# sensor-board_v1_23.net
KiCad netlist of a schematic drawn in EAGLE
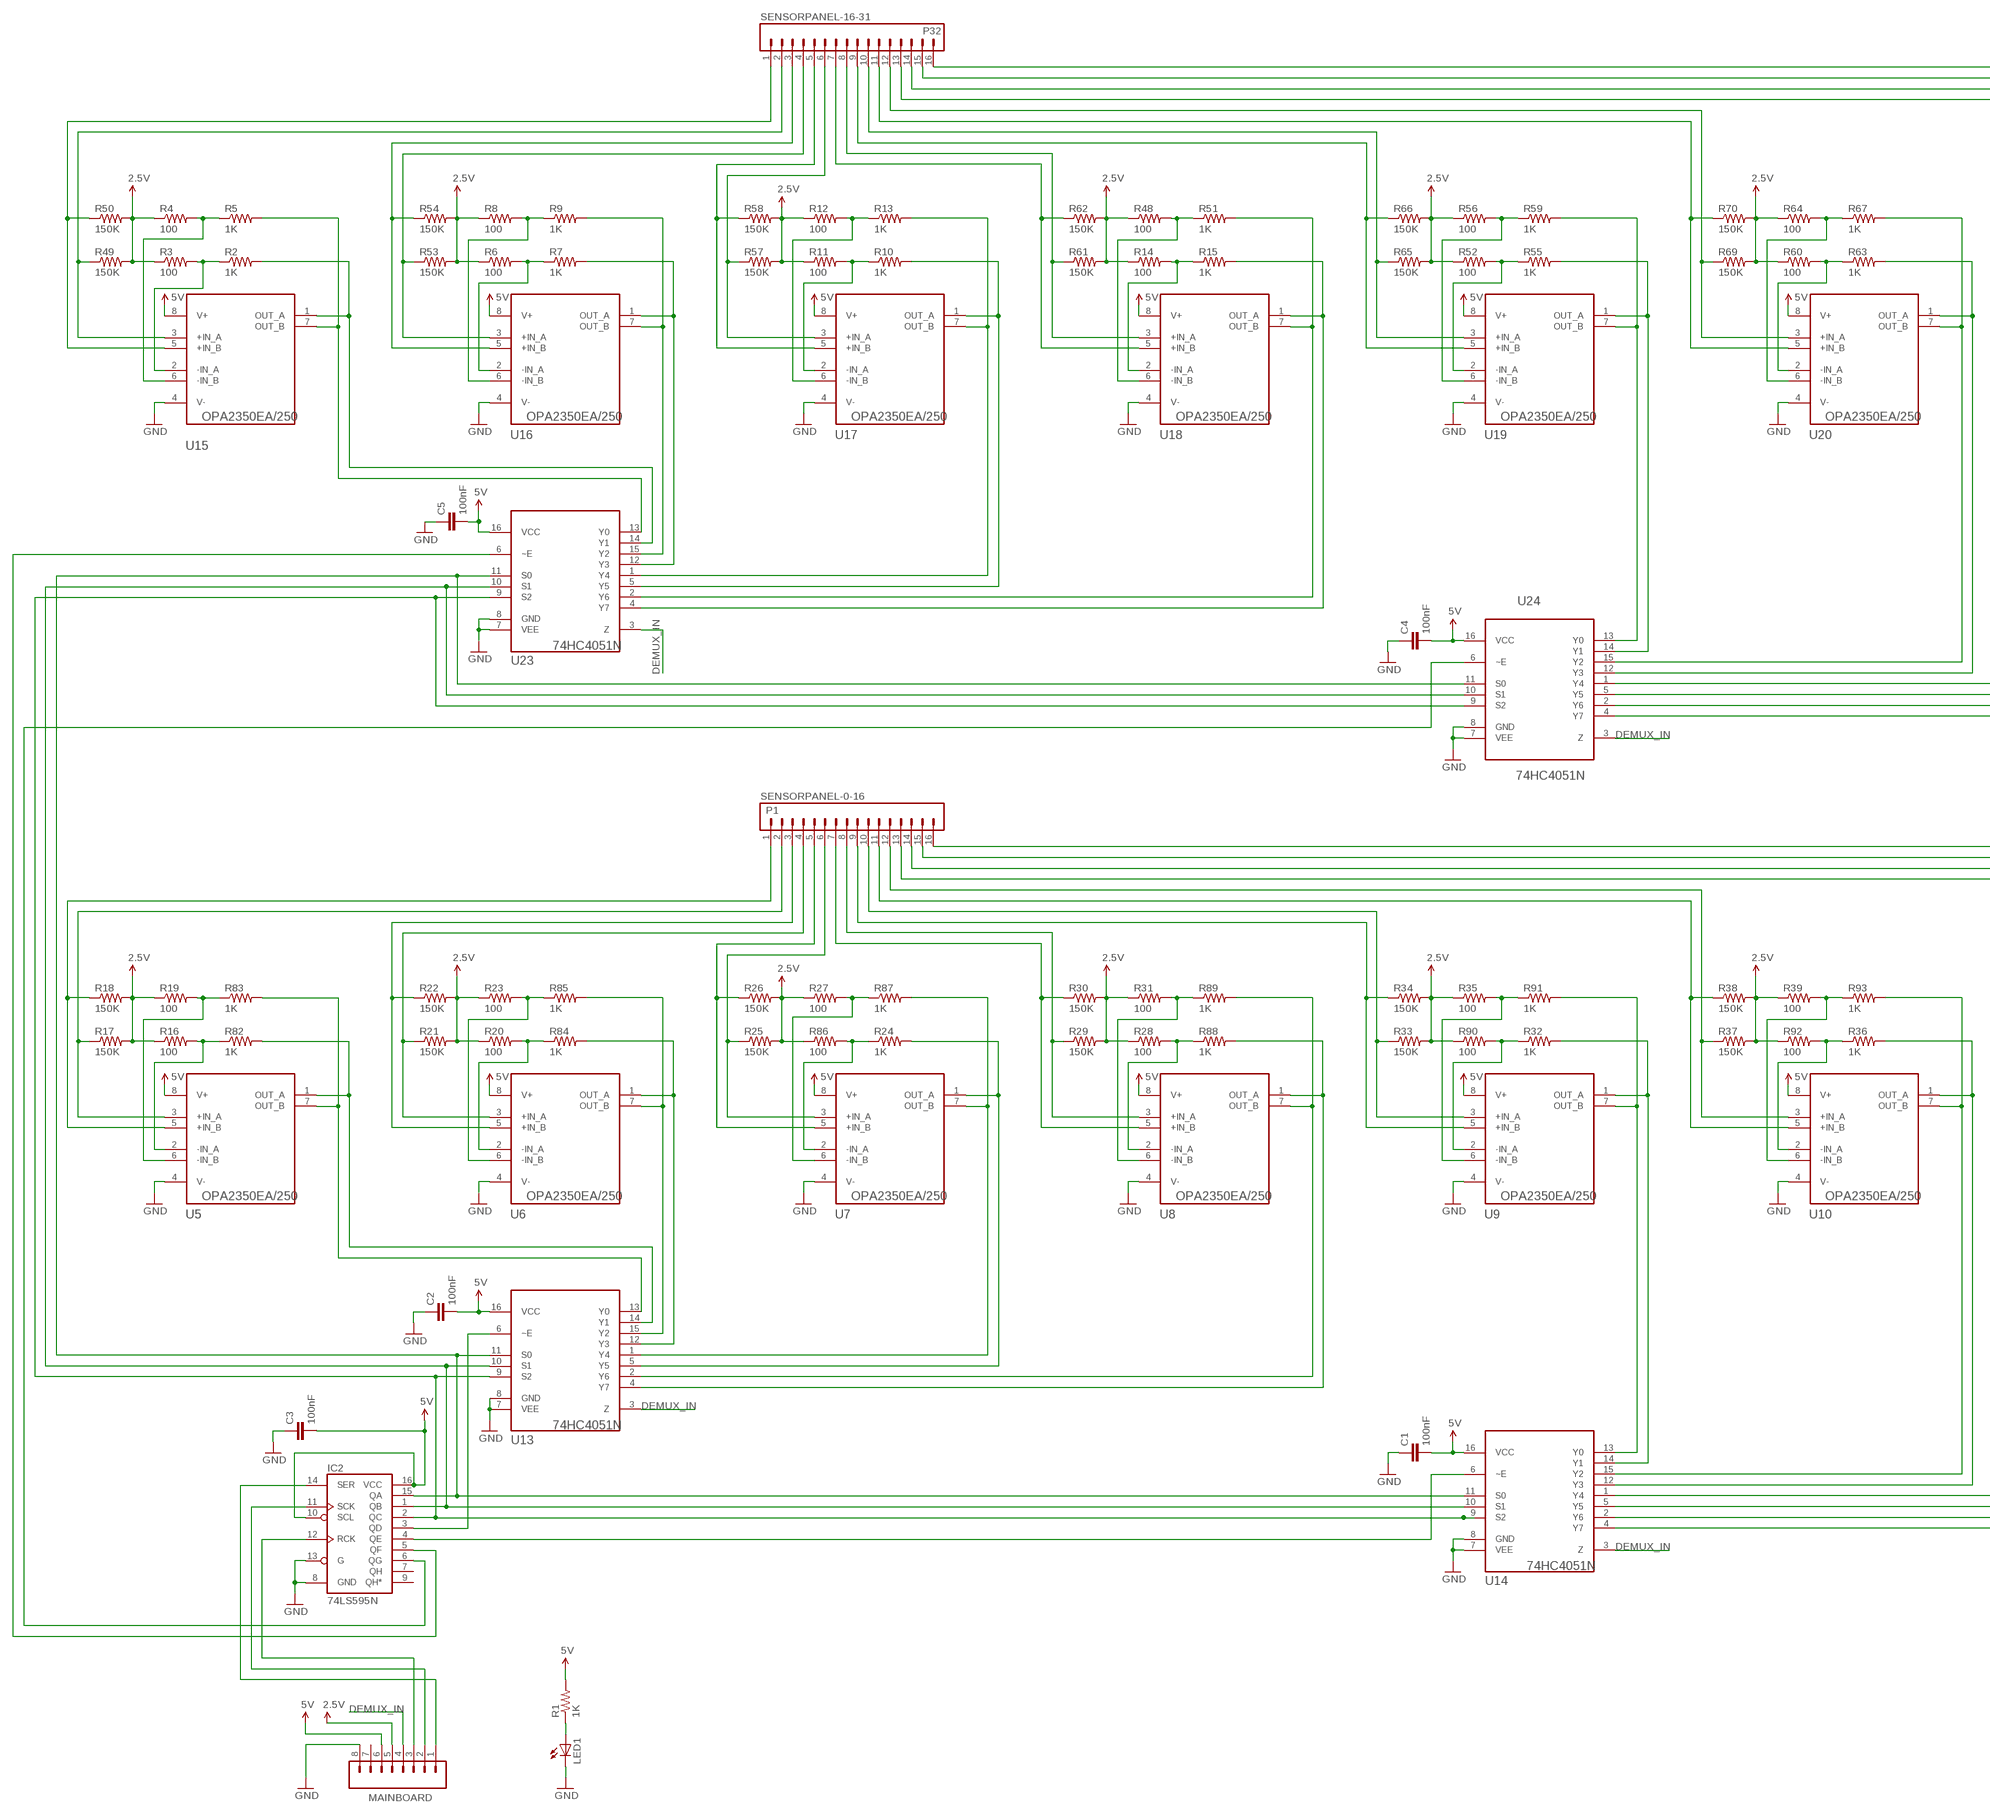
[diagram p0: schematic, sheet 1, part 1 of 2]
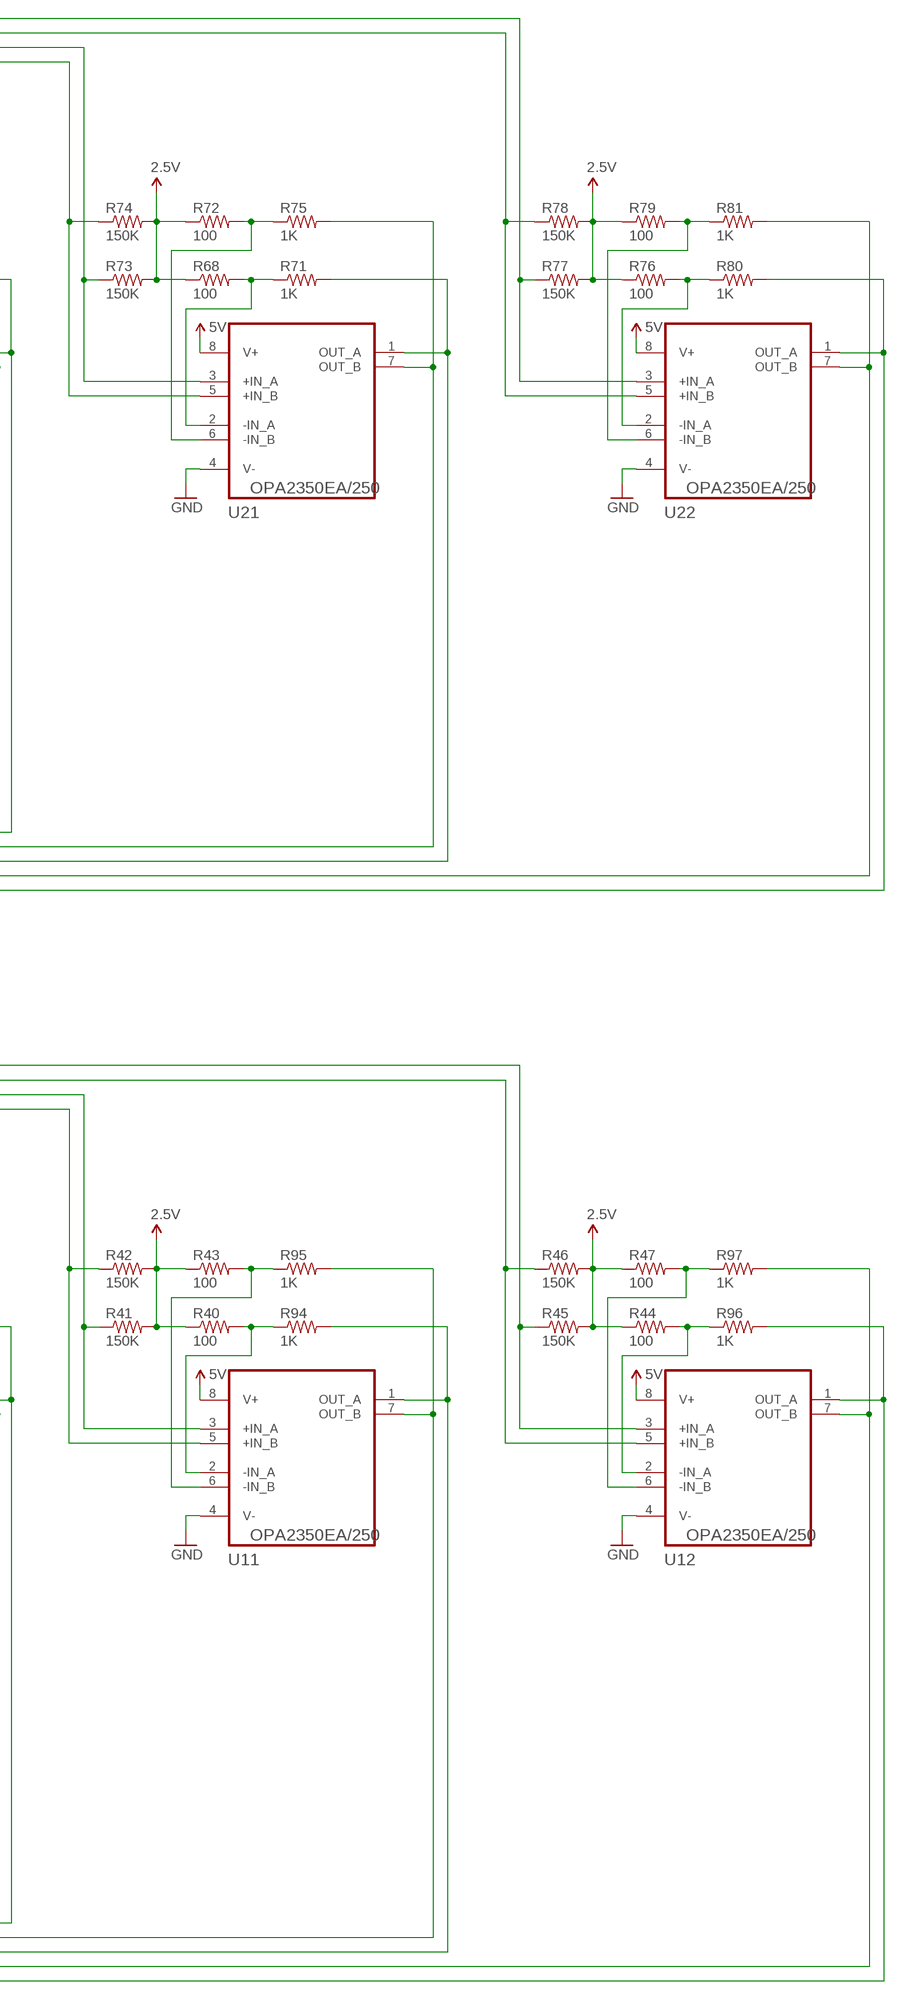
[diagram p1: schematic, sheet 1, part 2 of 2]

(export (version "E")
  (design (tool "Eeschema 10.0.6"))
  (components
    (comp (ref "C1")
      (value "100nF")
      (footprint "eagle-import:CAP-PTH-SMALL")
      (libsource (lib "eagle-import") (part "CAPPTH"))
    )
    (comp (ref "C2")
      (value "100nF")
      (footprint "eagle-import:CAP-PTH-SMALL")
      (libsource (lib "eagle-import") (part "CAPPTH"))
    )
    (comp (ref "C3")
      (value "100nF")
      (footprint "eagle-import:CAP-PTH-SMALL")
      (libsource (lib "eagle-import") (part "CAPPTH"))
    )
    (comp (ref "C4")
      (value "100nF")
      (footprint "eagle-import:CAP-PTH-SMALL")
      (libsource (lib "eagle-import") (part "CAPPTH"))
    )
    (comp (ref "C5")
      (value "100nF")
      (footprint "eagle-import:CAP-PTH-SMALL")
      (libsource (lib "eagle-import") (part "CAPPTH"))
    )
    (comp (ref "IC2")
      (value "74LS595N")
      (footprint "eagle-import:DIL16")
      (libsource (lib "eagle-import") (part "74595NLS"))
    )
    (comp (ref "LED1")
      (value "LED0603")
      (footprint "eagle-import:LED-0603")
      (libsource (lib "eagle-import") (part "LED0603"))
    )
    (comp (ref "MAINBOARD")
      (value "M08LONGPADS")
      (footprint "eagle-import:1X08_LONGPADS")
      (libsource (lib "eagle-import") (part "M08LONGPADS"))
    )
    (comp (ref "R1")
      (value "1K")
      (footprint "eagle-import:0805")
      (libsource (lib "eagle-import") (part "RESISTOR0805-RES"))
    )
    (comp (ref "R2")
      (value "1K")
      (footprint "eagle-import:0805")
      (libsource (lib "eagle-import") (part "RESISTOR0805-RES"))
    )
    (comp (ref "R3")
      (value "100")
      (footprint "eagle-import:0805")
      (libsource (lib "eagle-import") (part "RESISTOR0805-RES"))
    )
    (comp (ref "R4")
      (value "100")
      (footprint "eagle-import:0805")
      (libsource (lib "eagle-import") (part "RESISTOR0805-RES"))
    )
    (comp (ref "R5")
      (value "1K")
      (footprint "eagle-import:0805")
      (libsource (lib "eagle-import") (part "RESISTOR0805-RES"))
    )
    (comp (ref "R6")
      (value "100")
      (footprint "eagle-import:0805")
      (libsource (lib "eagle-import") (part "RESISTOR0805-RES"))
    )
    (comp (ref "R7")
      (value "1K")
      (footprint "eagle-import:0805")
      (libsource (lib "eagle-import") (part "RESISTOR0805-RES"))
    )
    (comp (ref "R8")
      (value "100")
      (footprint "eagle-import:0805")
      (libsource (lib "eagle-import") (part "RESISTOR0805-RES"))
    )
    (comp (ref "R9")
      (value "1K")
      (footprint "eagle-import:0805")
      (libsource (lib "eagle-import") (part "RESISTOR0805-RES"))
    )
    (comp (ref "R10")
      (value "1K")
      (footprint "eagle-import:0805")
      (libsource (lib "eagle-import") (part "RESISTOR0805-RES"))
    )
    (comp (ref "R11")
      (value "100")
      (footprint "eagle-import:0805")
      (libsource (lib "eagle-import") (part "RESISTOR0805-RES"))
    )
    (comp (ref "R12")
      (value "100")
      (footprint "eagle-import:0805")
      (libsource (lib "eagle-import") (part "RESISTOR0805-RES"))
    )
    (comp (ref "R13")
      (value "1K")
      (footprint "eagle-import:0805")
      (libsource (lib "eagle-import") (part "RESISTOR0805-RES"))
    )
    (comp (ref "R14")
      (value "100")
      (footprint "eagle-import:0805")
      (libsource (lib "eagle-import") (part "RESISTOR0805-RES"))
    )
    (comp (ref "R15")
      (value "1K")
      (footprint "eagle-import:0805")
      (libsource (lib "eagle-import") (part "RESISTOR0805-RES"))
    )
    (comp (ref "R16")
      (value "100")
      (footprint "eagle-import:0805")
      (libsource (lib "eagle-import") (part "RESISTOR0805-RES"))
    )
    (comp (ref "R17")
      (value "150K")
      (footprint "eagle-import:0805")
      (libsource (lib "eagle-import") (part "RESISTOR0805-RES"))
    )
    (comp (ref "R18")
      (value "150K")
      (footprint "eagle-import:0805")
      (libsource (lib "eagle-import") (part "RESISTOR0805-RES"))
    )
    (comp (ref "R19")
      (value "100")
      (footprint "eagle-import:0805")
      (libsource (lib "eagle-import") (part "RESISTOR0805-RES"))
    )
    (comp (ref "R20")
      (value "100")
      (footprint "eagle-import:0805")
      (libsource (lib "eagle-import") (part "RESISTOR0805-RES"))
    )
    (comp (ref "R21")
      (value "150K")
      (footprint "eagle-import:0805")
      (libsource (lib "eagle-import") (part "RESISTOR0805-RES"))
    )
    (comp (ref "R22")
      (value "150K")
      (footprint "eagle-import:0805")
      (libsource (lib "eagle-import") (part "RESISTOR0805-RES"))
    )
    (comp (ref "R23")
      (value "100")
      (footprint "eagle-import:0805")
      (libsource (lib "eagle-import") (part "RESISTOR0805-RES"))
    )
    (comp (ref "R24")
      (value "1K")
      (footprint "eagle-import:0805")
      (libsource (lib "eagle-import") (part "RESISTOR0805-RES"))
    )
    (comp (ref "R25")
      (value "150K")
      (footprint "eagle-import:0805")
      (libsource (lib "eagle-import") (part "RESISTOR0805-RES"))
    )
    (comp (ref "R26")
      (value "150K")
      (footprint "eagle-import:0805")
      (libsource (lib "eagle-import") (part "RESISTOR0805-RES"))
    )
    (comp (ref "R27")
      (value "100")
      (footprint "eagle-import:0805")
      (libsource (lib "eagle-import") (part "RESISTOR0805-RES"))
    )
    (comp (ref "R28")
      (value "100")
      (footprint "eagle-import:0805")
      (libsource (lib "eagle-import") (part "RESISTOR0805-RES"))
    )
    (comp (ref "R29")
      (value "150K")
      (footprint "eagle-import:0805")
      (libsource (lib "eagle-import") (part "RESISTOR0805-RES"))
    )
    (comp (ref "R30")
      (value "150K")
      (footprint "eagle-import:0805")
      (libsource (lib "eagle-import") (part "RESISTOR0805-RES"))
    )
    (comp (ref "R31")
      (value "100")
      (footprint "eagle-import:0805")
      (libsource (lib "eagle-import") (part "RESISTOR0805-RES"))
    )
    (comp (ref "R32")
      (value "1K")
      (footprint "eagle-import:0805")
      (libsource (lib "eagle-import") (part "RESISTOR0805-RES"))
    )
    (comp (ref "R33")
      (value "150K")
      (footprint "eagle-import:0805")
      (libsource (lib "eagle-import") (part "RESISTOR0805-RES"))
    )
    (comp (ref "R34")
      (value "150K")
      (footprint "eagle-import:0805")
      (libsource (lib "eagle-import") (part "RESISTOR0805-RES"))
    )
    (comp (ref "R35")
      (value "100")
      (footprint "eagle-import:0805")
      (libsource (lib "eagle-import") (part "RESISTOR0805-RES"))
    )
    (comp (ref "R36")
      (value "1K")
      (footprint "eagle-import:0805")
      (libsource (lib "eagle-import") (part "RESISTOR0805-RES"))
    )
    (comp (ref "R37")
      (value "150K")
      (footprint "eagle-import:0805")
      (libsource (lib "eagle-import") (part "RESISTOR0805-RES"))
    )
    (comp (ref "R38")
      (value "150K")
      (footprint "eagle-import:0805")
      (libsource (lib "eagle-import") (part "RESISTOR0805-RES"))
    )
    (comp (ref "R39")
      (value "100")
      (footprint "eagle-import:0805")
      (libsource (lib "eagle-import") (part "RESISTOR0805-RES"))
    )
    (comp (ref "R40")
      (value "100")
      (footprint "eagle-import:0805")
      (libsource (lib "eagle-import") (part "RESISTOR0805-RES"))
    )
    (comp (ref "R41")
      (value "150K")
      (footprint "eagle-import:0805")
      (libsource (lib "eagle-import") (part "RESISTOR0805-RES"))
    )
    (comp (ref "R42")
      (value "150K")
      (footprint "eagle-import:0805")
      (libsource (lib "eagle-import") (part "RESISTOR0805-RES"))
    )
    (comp (ref "R43")
      (value "100")
      (footprint "eagle-import:0805")
      (libsource (lib "eagle-import") (part "RESISTOR0805-RES"))
    )
    (comp (ref "R44")
      (value "100")
      (footprint "eagle-import:0805")
      (libsource (lib "eagle-import") (part "RESISTOR0805-RES"))
    )
    (comp (ref "R45")
      (value "150K")
      (footprint "eagle-import:0805")
      (libsource (lib "eagle-import") (part "RESISTOR0805-RES"))
    )
    (comp (ref "R46")
      (value "150K")
      (footprint "eagle-import:0805")
      (libsource (lib "eagle-import") (part "RESISTOR0805-RES"))
    )
    (comp (ref "R47")
      (value "100")
      (footprint "eagle-import:0805")
      (libsource (lib "eagle-import") (part "RESISTOR0805-RES"))
    )
    (comp (ref "R48")
      (value "100")
      (footprint "eagle-import:0805")
      (libsource (lib "eagle-import") (part "RESISTOR0805-RES"))
    )
    (comp (ref "R49")
      (value "150K")
      (footprint "eagle-import:0805")
      (libsource (lib "eagle-import") (part "RESISTOR0805-RES"))
    )
    (comp (ref "R50")
      (value "150K")
      (footprint "eagle-import:0805")
      (libsource (lib "eagle-import") (part "RESISTOR0805-RES"))
    )
    (comp (ref "R51")
      (value "1K")
      (footprint "eagle-import:0805")
      (libsource (lib "eagle-import") (part "RESISTOR0805-RES"))
    )
    (comp (ref "R52")
      (value "100")
      (footprint "eagle-import:0805")
      (libsource (lib "eagle-import") (part "RESISTOR0805-RES"))
    )
    (comp (ref "R53")
      (value "150K")
      (footprint "eagle-import:0805")
      (libsource (lib "eagle-import") (part "RESISTOR0805-RES"))
    )
    (comp (ref "R54")
      (value "150K")
      (footprint "eagle-import:0805")
      (libsource (lib "eagle-import") (part "RESISTOR0805-RES"))
    )
    (comp (ref "R55")
      (value "1K")
      (footprint "eagle-import:0805")
      (libsource (lib "eagle-import") (part "RESISTOR0805-RES"))
    )
    (comp (ref "R56")
      (value "100")
      (footprint "eagle-import:0805")
      (libsource (lib "eagle-import") (part "RESISTOR0805-RES"))
    )
    (comp (ref "R57")
      (value "150K")
      (footprint "eagle-import:0805")
      (libsource (lib "eagle-import") (part "RESISTOR0805-RES"))
    )
    (comp (ref "R58")
      (value "150K")
      (footprint "eagle-import:0805")
      (libsource (lib "eagle-import") (part "RESISTOR0805-RES"))
    )
    (comp (ref "R59")
      (value "1K")
      (footprint "eagle-import:0805")
      (libsource (lib "eagle-import") (part "RESISTOR0805-RES"))
    )
    (comp (ref "R60")
      (value "100")
      (footprint "eagle-import:0805")
      (libsource (lib "eagle-import") (part "RESISTOR0805-RES"))
    )
    (comp (ref "R61")
      (value "150K")
      (footprint "eagle-import:0805")
      (libsource (lib "eagle-import") (part "RESISTOR0805-RES"))
    )
    (comp (ref "R62")
      (value "150K")
      (footprint "eagle-import:0805")
      (libsource (lib "eagle-import") (part "RESISTOR0805-RES"))
    )
    (comp (ref "R63")
      (value "1K")
      (footprint "eagle-import:0805")
      (libsource (lib "eagle-import") (part "RESISTOR0805-RES"))
    )
    (comp (ref "R64")
      (value "100")
      (footprint "eagle-import:0805")
      (libsource (lib "eagle-import") (part "RESISTOR0805-RES"))
    )
    (comp (ref "R65")
      (value "150K")
      (footprint "eagle-import:0805")
      (libsource (lib "eagle-import") (part "RESISTOR0805-RES"))
    )
    (comp (ref "R66")
      (value "150K")
      (footprint "eagle-import:0805")
      (libsource (lib "eagle-import") (part "RESISTOR0805-RES"))
    )
    (comp (ref "R67")
      (value "1K")
      (footprint "eagle-import:0805")
      (libsource (lib "eagle-import") (part "RESISTOR0805-RES"))
    )
    (comp (ref "R68")
      (value "100")
      (footprint "eagle-import:0805")
      (libsource (lib "eagle-import") (part "RESISTOR0805-RES"))
    )
    (comp (ref "R69")
      (value "150K")
      (footprint "eagle-import:0805")
      (libsource (lib "eagle-import") (part "RESISTOR0805-RES"))
    )
    (comp (ref "R70")
      (value "150K")
      (footprint "eagle-import:0805")
      (libsource (lib "eagle-import") (part "RESISTOR0805-RES"))
    )
    (comp (ref "R71")
      (value "1K")
      (footprint "eagle-import:0805")
      (libsource (lib "eagle-import") (part "RESISTOR0805-RES"))
    )
    (comp (ref "R72")
      (value "100")
      (footprint "eagle-import:0805")
      (libsource (lib "eagle-import") (part "RESISTOR0805-RES"))
    )
    (comp (ref "R73")
      (value "150K")
      (footprint "eagle-import:0805")
      (libsource (lib "eagle-import") (part "RESISTOR0805-RES"))
    )
    (comp (ref "R74")
      (value "150K")
      (footprint "eagle-import:0805")
      (libsource (lib "eagle-import") (part "RESISTOR0805-RES"))
    )
    (comp (ref "R75")
      (value "1K")
      (footprint "eagle-import:0805")
      (libsource (lib "eagle-import") (part "RESISTOR0805-RES"))
    )
    (comp (ref "R76")
      (value "100")
      (footprint "eagle-import:0805")
      (libsource (lib "eagle-import") (part "RESISTOR0805-RES"))
    )
    (comp (ref "R77")
      (value "150K")
      (footprint "eagle-import:0805")
      (libsource (lib "eagle-import") (part "RESISTOR0805-RES"))
    )
    (comp (ref "R78")
      (value "150K")
      (footprint "eagle-import:0805")
      (libsource (lib "eagle-import") (part "RESISTOR0805-RES"))
    )
    (comp (ref "R79")
      (value "100")
      (footprint "eagle-import:0805")
      (libsource (lib "eagle-import") (part "RESISTOR0805-RES"))
    )
    (comp (ref "R80")
      (value "1K")
      (footprint "eagle-import:0805")
      (libsource (lib "eagle-import") (part "RESISTOR0805-RES"))
    )
    (comp (ref "R81")
      (value "1K")
      (footprint "eagle-import:0805")
      (libsource (lib "eagle-import") (part "RESISTOR0805-RES"))
    )
    (comp (ref "R82")
      (value "1K")
      (footprint "eagle-import:0805")
      (libsource (lib "eagle-import") (part "RESISTOR0805-RES"))
    )
    (comp (ref "R83")
      (value "1K")
      (footprint "eagle-import:0805")
      (libsource (lib "eagle-import") (part "RESISTOR0805-RES"))
    )
    (comp (ref "R84")
      (value "1K")
      (footprint "eagle-import:0805")
      (libsource (lib "eagle-import") (part "RESISTOR0805-RES"))
    )
    (comp (ref "R85")
      (value "1K")
      (footprint "eagle-import:0805")
      (libsource (lib "eagle-import") (part "RESISTOR0805-RES"))
    )
    (comp (ref "R86")
      (value "100")
      (footprint "eagle-import:0805")
      (libsource (lib "eagle-import") (part "RESISTOR0805-RES"))
    )
    (comp (ref "R87")
      (value "1K")
      (footprint "eagle-import:0805")
      (libsource (lib "eagle-import") (part "RESISTOR0805-RES"))
    )
    (comp (ref "R88")
      (value "1K")
      (footprint "eagle-import:0805")
      (libsource (lib "eagle-import") (part "RESISTOR0805-RES"))
    )
    (comp (ref "R89")
      (value "1K")
      (footprint "eagle-import:0805")
      (libsource (lib "eagle-import") (part "RESISTOR0805-RES"))
    )
    (comp (ref "R90")
      (value "100")
      (footprint "eagle-import:0805")
      (libsource (lib "eagle-import") (part "RESISTOR0805-RES"))
    )
    (comp (ref "R91")
      (value "1K")
      (footprint "eagle-import:0805")
      (libsource (lib "eagle-import") (part "RESISTOR0805-RES"))
    )
    (comp (ref "R92")
      (value "100")
      (footprint "eagle-import:0805")
      (libsource (lib "eagle-import") (part "RESISTOR0805-RES"))
    )
    (comp (ref "R93")
      (value "1K")
      (footprint "eagle-import:0805")
      (libsource (lib "eagle-import") (part "RESISTOR0805-RES"))
    )
    (comp (ref "R94")
      (value "1K")
      (footprint "eagle-import:0805")
      (libsource (lib "eagle-import") (part "RESISTOR0805-RES"))
    )
    (comp (ref "R95")
      (value "1K")
      (footprint "eagle-import:0805")
      (libsource (lib "eagle-import") (part "RESISTOR0805-RES"))
    )
    (comp (ref "R96")
      (value "1K")
      (footprint "eagle-import:0805")
      (libsource (lib "eagle-import") (part "RESISTOR0805-RES"))
    )
    (comp (ref "R97")
      (value "1K")
      (footprint "eagle-import:0805")
      (libsource (lib "eagle-import") (part "RESISTOR0805-RES"))
    )
    (comp (ref "SENSORPANEL-0-16")
      (value "P1")
      (footprint "eagle-import:1X16_LOCK")
      (libsource (lib "eagle-import") (part "M16LOCK"))
    )
    (comp (ref "SENSORPANEL-16-31")
      (value "P32")
      (footprint "eagle-import:1X16_LOCK")
      (libsource (lib "eagle-import") (part "M16LOCK"))
    )
    (comp (ref "U5")
      (value "OPA2350EA/250")
      (footprint "eagle-import:SOP65P490X110-8N")
      (libsource (lib "eagle-import") (part "OPA2350EA/250"))
    )
    (comp (ref "U6")
      (value "OPA2350EA/250")
      (footprint "eagle-import:SOP65P490X110-8N")
      (libsource (lib "eagle-import") (part "OPA2350EA/250"))
    )
    (comp (ref "U7")
      (value "OPA2350EA/250")
      (footprint "eagle-import:SOP65P490X110-8N")
      (libsource (lib "eagle-import") (part "OPA2350EA/250"))
    )
    (comp (ref "U8")
      (value "OPA2350EA/250")
      (footprint "eagle-import:SOP65P490X110-8N")
      (libsource (lib "eagle-import") (part "OPA2350EA/250"))
    )
    (comp (ref "U9")
      (value "OPA2350EA/250")
      (footprint "eagle-import:SOP65P490X110-8N")
      (libsource (lib "eagle-import") (part "OPA2350EA/250"))
    )
    (comp (ref "U10")
      (value "OPA2350EA/250")
      (footprint "eagle-import:SOP65P490X110-8N")
      (libsource (lib "eagle-import") (part "OPA2350EA/250"))
    )
    (comp (ref "U11")
      (value "OPA2350EA/250")
      (footprint "eagle-import:SOP65P490X110-8N")
      (libsource (lib "eagle-import") (part "OPA2350EA/250"))
    )
    (comp (ref "U12")
      (value "OPA2350EA/250")
      (footprint "eagle-import:SOP65P490X110-8N")
      (libsource (lib "eagle-import") (part "OPA2350EA/250"))
    )
    (comp (ref "U13")
      (value "74HC4051N")
      (footprint "eagle-import:DIP254P762X420-16")
      (libsource (lib "eagle-import") (part "74HC4051N"))
    )
    (comp (ref "U14")
      (value "74HC4051N")
      (footprint "eagle-import:DIP254P762X420-16")
      (libsource (lib "eagle-import") (part "74HC4051N"))
    )
    (comp (ref "U15")
      (value "OPA2350EA/250")
      (footprint "eagle-import:SOP65P490X110-8N")
      (libsource (lib "eagle-import") (part "OPA2350EA/250"))
    )
    (comp (ref "U16")
      (value "OPA2350EA/250")
      (footprint "eagle-import:SOP65P490X110-8N")
      (libsource (lib "eagle-import") (part "OPA2350EA/250"))
    )
    (comp (ref "U17")
      (value "OPA2350EA/250")
      (footprint "eagle-import:SOP65P490X110-8N")
      (libsource (lib "eagle-import") (part "OPA2350EA/250"))
    )
    (comp (ref "U18")
      (value "OPA2350EA/250")
      (footprint "eagle-import:SOP65P490X110-8N")
      (libsource (lib "eagle-import") (part "OPA2350EA/250"))
    )
    (comp (ref "U19")
      (value "OPA2350EA/250")
      (footprint "eagle-import:SOP65P490X110-8N")
      (libsource (lib "eagle-import") (part "OPA2350EA/250"))
    )
    (comp (ref "U20")
      (value "OPA2350EA/250")
      (footprint "eagle-import:SOP65P490X110-8N")
      (libsource (lib "eagle-import") (part "OPA2350EA/250"))
    )
    (comp (ref "U21")
      (value "OPA2350EA/250")
      (footprint "eagle-import:SOP65P490X110-8N")
      (libsource (lib "eagle-import") (part "OPA2350EA/250"))
    )
    (comp (ref "U22")
      (value "OPA2350EA/250")
      (footprint "eagle-import:SOP65P490X110-8N")
      (libsource (lib "eagle-import") (part "OPA2350EA/250"))
    )
    (comp (ref "U23")
      (value "74HC4051N")
      (footprint "eagle-import:DIP254P762X420-16")
      (libsource (lib "eagle-import") (part "74HC4051N"))
    )
    (comp (ref "U24")
      (value "74HC4051N")
      (footprint "eagle-import:DIP254P762X420-16")
      (libsource (lib "eagle-import") (part "74HC4051N"))
    )
  )
  (nets
    (net (code "1") (name "/DEMUX_IN") (class "Default")
      (node (ref "MAINBOARD") (pin "4") (pinfunction "4_4") (pintype "passive"))
      (node (ref "U13") (pin "3") (pinfunction "Z_3") (pintype "bidirectional"))
      (node (ref "U14") (pin "3") (pinfunction "Z_3") (pintype "bidirectional"))
      (node (ref "U23") (pin "3") (pinfunction "Z_3") (pintype "bidirectional"))
      (node (ref "U24") (pin "3") (pinfunction "Z_3") (pintype "bidirectional"))
    )
    (net (code "2") (name "2.5V") (class "Default")
      (node (ref "MAINBOARD") (pin "5") (pinfunction "5_5") (pintype "passive"))
      (node (ref "R11") (pin "1") (pinfunction "1_1") (pintype "passive"))
      (node (ref "R12") (pin "1") (pinfunction "1_1") (pintype "passive"))
      (node (ref "R14") (pin "1") (pinfunction "1_1") (pintype "passive"))
      (node (ref "R16") (pin "1") (pinfunction "1_1") (pintype "passive"))
      (node (ref "R17") (pin "2") (pinfunction "2_2") (pintype "passive"))
      (node (ref "R18") (pin "2") (pinfunction "2_2") (pintype "passive"))
      (node (ref "R19") (pin "1") (pinfunction "1_1") (pintype "passive"))
      (node (ref "R20") (pin "1") (pinfunction "1_1") (pintype "passive"))
      (node (ref "R21") (pin "2") (pinfunction "2_2") (pintype "passive"))
      (node (ref "R22") (pin "2") (pinfunction "2_2") (pintype "passive"))
      (node (ref "R23") (pin "1") (pinfunction "1_1") (pintype "passive"))
      (node (ref "R25") (pin "2") (pinfunction "2_2") (pintype "passive"))
      (node (ref "R26") (pin "2") (pinfunction "2_2") (pintype "passive"))
      (node (ref "R27") (pin "1") (pinfunction "1_1") (pintype "passive"))
      (node (ref "R28") (pin "1") (pinfunction "1_1") (pintype "passive"))
      (node (ref "R29") (pin "2") (pinfunction "2_2") (pintype "passive"))
      (node (ref "R3") (pin "1") (pinfunction "1_1") (pintype "passive"))
      (node (ref "R30") (pin "2") (pinfunction "2_2") (pintype "passive"))
      (node (ref "R31") (pin "1") (pinfunction "1_1") (pintype "passive"))
      (node (ref "R33") (pin "2") (pinfunction "2_2") (pintype "passive"))
      (node (ref "R34") (pin "2") (pinfunction "2_2") (pintype "passive"))
      (node (ref "R35") (pin "1") (pinfunction "1_1") (pintype "passive"))
      (node (ref "R37") (pin "2") (pinfunction "2_2") (pintype "passive"))
      (node (ref "R38") (pin "2") (pinfunction "2_2") (pintype "passive"))
      (node (ref "R39") (pin "1") (pinfunction "1_1") (pintype "passive"))
      (node (ref "R4") (pin "1") (pinfunction "1_1") (pintype "passive"))
      (node (ref "R40") (pin "1") (pinfunction "1_1") (pintype "passive"))
      (node (ref "R41") (pin "2") (pinfunction "2_2") (pintype "passive"))
      (node (ref "R42") (pin "2") (pinfunction "2_2") (pintype "passive"))
      (node (ref "R43") (pin "1") (pinfunction "1_1") (pintype "passive"))
      (node (ref "R44") (pin "1") (pinfunction "1_1") (pintype "passive"))
      (node (ref "R45") (pin "2") (pinfunction "2_2") (pintype "passive"))
      (node (ref "R46") (pin "2") (pinfunction "2_2") (pintype "passive"))
      (node (ref "R47") (pin "1") (pinfunction "1_1") (pintype "passive"))
      (node (ref "R48") (pin "1") (pinfunction "1_1") (pintype "passive"))
      (node (ref "R49") (pin "2") (pinfunction "2_2") (pintype "passive"))
      (node (ref "R50") (pin "2") (pinfunction "2_2") (pintype "passive"))
      (node (ref "R52") (pin "1") (pinfunction "1_1") (pintype "passive"))
      (node (ref "R53") (pin "2") (pinfunction "2_2") (pintype "passive"))
      (node (ref "R54") (pin "2") (pinfunction "2_2") (pintype "passive"))
      (node (ref "R56") (pin "1") (pinfunction "1_1") (pintype "passive"))
      (node (ref "R57") (pin "2") (pinfunction "2_2") (pintype "passive"))
      (node (ref "R58") (pin "2") (pinfunction "2_2") (pintype "passive"))
      (node (ref "R6") (pin "1") (pinfunction "1_1") (pintype "passive"))
      (node (ref "R60") (pin "1") (pinfunction "1_1") (pintype "passive"))
      (node (ref "R61") (pin "2") (pinfunction "2_2") (pintype "passive"))
      (node (ref "R62") (pin "2") (pinfunction "2_2") (pintype "passive"))
      (node (ref "R64") (pin "1") (pinfunction "1_1") (pintype "passive"))
      (node (ref "R65") (pin "2") (pinfunction "2_2") (pintype "passive"))
      (node (ref "R66") (pin "2") (pinfunction "2_2") (pintype "passive"))
      (node (ref "R68") (pin "1") (pinfunction "1_1") (pintype "passive"))
      (node (ref "R69") (pin "2") (pinfunction "2_2") (pintype "passive"))
      (node (ref "R70") (pin "2") (pinfunction "2_2") (pintype "passive"))
      (node (ref "R72") (pin "1") (pinfunction "1_1") (pintype "passive"))
      (node (ref "R73") (pin "2") (pinfunction "2_2") (pintype "passive"))
      (node (ref "R74") (pin "2") (pinfunction "2_2") (pintype "passive"))
      (node (ref "R76") (pin "1") (pinfunction "1_1") (pintype "passive"))
      (node (ref "R77") (pin "2") (pinfunction "2_2") (pintype "passive"))
      (node (ref "R78") (pin "2") (pinfunction "2_2") (pintype "passive"))
      (node (ref "R79") (pin "1") (pinfunction "1_1") (pintype "passive"))
      (node (ref "R8") (pin "1") (pinfunction "1_1") (pintype "passive"))
      (node (ref "R86") (pin "1") (pinfunction "1_1") (pintype "passive"))
      (node (ref "R90") (pin "1") (pinfunction "1_1") (pintype "passive"))
      (node (ref "R92") (pin "1") (pinfunction "1_1") (pintype "passive"))
    )
    (net (code "3") (name "5V") (class "Default")
      (node (ref "C1") (pin "2") (pinfunction "2_2") (pintype "passive"))
      (node (ref "C2") (pin "2") (pinfunction "2_2") (pintype "passive"))
      (node (ref "C3") (pin "2") (pinfunction "2_2") (pintype "passive"))
      (node (ref "C4") (pin "2") (pinfunction "2_2") (pintype "passive"))
      (node (ref "C5") (pin "2") (pinfunction "2_2") (pintype "passive"))
      (node (ref "IC2") (pin "10") (pinfunction "SCL_10") (pintype "input"))
      (node (ref "IC2") (pin "16") (pinfunction "VCC_16") (pintype "power_in"))
      (node (ref "MAINBOARD") (pin "6") (pinfunction "6_6") (pintype "passive"))
      (node (ref "R1") (pin "2") (pinfunction "2_2") (pintype "passive"))
      (node (ref "U10") (pin "8") (pinfunction "V+_8") (pintype "power_in"))
      (node (ref "U11") (pin "8") (pinfunction "V+_8") (pintype "power_in"))
      (node (ref "U12") (pin "8") (pinfunction "V+_8") (pintype "power_in"))
      (node (ref "U13") (pin "16") (pinfunction "VCC_16") (pintype "power_in"))
      (node (ref "U14") (pin "16") (pinfunction "VCC_16") (pintype "power_in"))
      (node (ref "U15") (pin "8") (pinfunction "V+_8") (pintype "power_in"))
      (node (ref "U16") (pin "8") (pinfunction "V+_8") (pintype "power_in"))
      (node (ref "U17") (pin "8") (pinfunction "V+_8") (pintype "power_in"))
      (node (ref "U18") (pin "8") (pinfunction "V+_8") (pintype "power_in"))
      (node (ref "U19") (pin "8") (pinfunction "V+_8") (pintype "power_in"))
      (node (ref "U20") (pin "8") (pinfunction "V+_8") (pintype "power_in"))
      (node (ref "U21") (pin "8") (pinfunction "V+_8") (pintype "power_in"))
      (node (ref "U22") (pin "8") (pinfunction "V+_8") (pintype "power_in"))
      (node (ref "U23") (pin "16") (pinfunction "VCC_16") (pintype "power_in"))
      (node (ref "U24") (pin "16") (pinfunction "VCC_16") (pintype "power_in"))
      (node (ref "U5") (pin "8") (pinfunction "V+_8") (pintype "power_in"))
      (node (ref "U6") (pin "8") (pinfunction "V+_8") (pintype "power_in"))
      (node (ref "U7") (pin "8") (pinfunction "V+_8") (pintype "power_in"))
      (node (ref "U8") (pin "8") (pinfunction "V+_8") (pintype "power_in"))
      (node (ref "U9") (pin "8") (pinfunction "V+_8") (pintype "power_in"))
    )
    (net (code "4") (name "GND") (class "Default")
      (node (ref "C1") (pin "1") (pinfunction "1_1") (pintype "passive"))
      (node (ref "C2") (pin "1") (pinfunction "1_1") (pintype "passive"))
      (node (ref "C3") (pin "1") (pinfunction "1_1") (pintype "passive"))
      (node (ref "C4") (pin "1") (pinfunction "1_1") (pintype "passive"))
      (node (ref "C5") (pin "1") (pinfunction "1_1") (pintype "passive"))
      (node (ref "IC2") (pin "13") (pinfunction "G_13") (pintype "input"))
      (node (ref "IC2") (pin "8") (pinfunction "GND_8") (pintype "power_in"))
      (node (ref "LED1") (pin "C") (pinfunction "C_C") (pintype "passive"))
      (node (ref "MAINBOARD") (pin "8") (pinfunction "8_8") (pintype "passive"))
      (node (ref "U10") (pin "4") (pinfunction "V-_4") (pintype "power_in"))
      (node (ref "U11") (pin "4") (pinfunction "V-_4") (pintype "power_in"))
      (node (ref "U12") (pin "4") (pinfunction "V-_4") (pintype "power_in"))
      (node (ref "U13") (pin "7") (pinfunction "VEE_7") (pintype "power_in"))
      (node (ref "U13") (pin "8") (pinfunction "GND_8") (pintype "passive"))
      (node (ref "U14") (pin "7") (pinfunction "VEE_7") (pintype "power_in"))
      (node (ref "U14") (pin "8") (pinfunction "GND_8") (pintype "passive"))
      (node (ref "U15") (pin "4") (pinfunction "V-_4") (pintype "power_in"))
      (node (ref "U16") (pin "4") (pinfunction "V-_4") (pintype "power_in"))
      (node (ref "U17") (pin "4") (pinfunction "V-_4") (pintype "power_in"))
      (node (ref "U18") (pin "4") (pinfunction "V-_4") (pintype "power_in"))
      (node (ref "U19") (pin "4") (pinfunction "V-_4") (pintype "power_in"))
      (node (ref "U20") (pin "4") (pinfunction "V-_4") (pintype "power_in"))
      (node (ref "U21") (pin "4") (pinfunction "V-_4") (pintype "power_in"))
      (node (ref "U22") (pin "4") (pinfunction "V-_4") (pintype "power_in"))
      (node (ref "U23") (pin "7") (pinfunction "VEE_7") (pintype "power_in"))
      (node (ref "U23") (pin "8") (pinfunction "GND_8") (pintype "passive"))
      (node (ref "U24") (pin "7") (pinfunction "VEE_7") (pintype "power_in"))
      (node (ref "U24") (pin "8") (pinfunction "GND_8") (pintype "passive"))
      (node (ref "U5") (pin "4") (pinfunction "V-_4") (pintype "power_in"))
      (node (ref "U6") (pin "4") (pinfunction "V-_4") (pintype "power_in"))
      (node (ref "U7") (pin "4") (pinfunction "V-_4") (pintype "power_in"))
      (node (ref "U8") (pin "4") (pinfunction "V-_4") (pintype "power_in"))
      (node (ref "U9") (pin "4") (pinfunction "V-_4") (pintype "power_in"))
    )
    (net (code "5") (name "Net-(IC2-QA)") (class "Default")
      (node (ref "IC2") (pin "15") (pinfunction "QA_15") (pintype "tri_state"))
      (node (ref "U13") (pin "11") (pinfunction "S0_11") (pintype "input"))
      (node (ref "U14") (pin "11") (pinfunction "S0_11") (pintype "input"))
      (node (ref "U23") (pin "11") (pinfunction "S0_11") (pintype "input"))
      (node (ref "U24") (pin "11") (pinfunction "S0_11") (pintype "input"))
    )
    (net (code "6") (name "Net-(IC2-QB)") (class "Default")
      (node (ref "IC2") (pin "1") (pinfunction "QB_1") (pintype "tri_state"))
      (node (ref "U13") (pin "10") (pinfunction "S1_10") (pintype "input"))
      (node (ref "U14") (pin "10") (pinfunction "S1_10") (pintype "input"))
      (node (ref "U23") (pin "10") (pinfunction "S1_10") (pintype "input"))
      (node (ref "U24") (pin "10") (pinfunction "S1_10") (pintype "input"))
    )
    (net (code "7") (name "Net-(IC2-QC)") (class "Default")
      (node (ref "IC2") (pin "2") (pinfunction "QC_2") (pintype "tri_state"))
      (node (ref "U13") (pin "9") (pinfunction "S2_9") (pintype "input"))
      (node (ref "U14") (pin "9") (pinfunction "S2_9") (pintype "input"))
      (node (ref "U23") (pin "9") (pinfunction "S2_9") (pintype "input"))
      (node (ref "U24") (pin "9") (pinfunction "S2_9") (pintype "input"))
    )
    (net (code "8") (name "Net-(IC2-QD)") (class "Default")
      (node (ref "IC2") (pin "3") (pinfunction "QD_3") (pintype "tri_state"))
      (node (ref "U13") (pin "6") (pinfunction "~{E}_6") (pintype "input"))
    )
    (net (code "9") (name "Net-(IC2-QE)") (class "Default")
      (node (ref "IC2") (pin "4") (pinfunction "QE_4") (pintype "tri_state"))
      (node (ref "U14") (pin "6") (pinfunction "~{E}_6") (pintype "input"))
    )
    (net (code "10") (name "Net-(IC2-QF)") (class "Default")
      (node (ref "IC2") (pin "5") (pinfunction "QF_5") (pintype "tri_state"))
      (node (ref "U23") (pin "6") (pinfunction "~{E}_6") (pintype "input"))
    )
    (net (code "11") (name "Net-(IC2-QG)") (class "Default")
      (node (ref "IC2") (pin "6") (pinfunction "QG_6") (pintype "tri_state"))
      (node (ref "U24") (pin "6") (pinfunction "~{E}_6") (pintype "input"))
    )
    (net (code "12") (name "Net-(IC2-RCK)") (class "Default")
      (node (ref "IC2") (pin "12") (pinfunction "RCK_12") (pintype "input"))
      (node (ref "MAINBOARD") (pin "3") (pinfunction "3_3") (pintype "passive"))
    )
    (net (code "13") (name "Net-(IC2-SCK)") (class "Default")
      (node (ref "IC2") (pin "11") (pinfunction "SCK_11") (pintype "input"))
      (node (ref "MAINBOARD") (pin "2") (pinfunction "2_2") (pintype "passive"))
    )
    (net (code "14") (name "Net-(IC2-SER)") (class "Default")
      (node (ref "IC2") (pin "14") (pinfunction "SER_14") (pintype "input"))
      (node (ref "MAINBOARD") (pin "1") (pinfunction "1_1") (pintype "passive"))
    )
    (net (code "15") (name "Net-(LED1-PadA)") (class "Default")
      (node (ref "LED1") (pin "A") (pinfunction "A_A") (pintype "passive"))
      (node (ref "R1") (pin "1") (pinfunction "1_1") (pintype "passive"))
    )
    (net (code "16") (name "Net-(U5-+IN_A)") (class "Default")
      (node (ref "R17") (pin "1") (pinfunction "1_1") (pintype "passive"))
      (node (ref "SENSORPANEL-0-16") (pin "2") (pinfunction "2_2") (pintype "passive"))
      (node (ref "U5") (pin "3") (pinfunction "+IN_A_3") (pintype "input"))
    )
    (net (code "17") (name "Net-(U5-+IN_B)") (class "Default")
      (node (ref "R18") (pin "1") (pinfunction "1_1") (pintype "passive"))
      (node (ref "SENSORPANEL-0-16") (pin "1") (pinfunction "1_1") (pintype "passive"))
      (node (ref "U5") (pin "5") (pinfunction "+IN_B_5") (pintype "input"))
    )
    (net (code "18") (name "Net-(U5--IN_A)") (class "Default")
      (node (ref "R16") (pin "2") (pinfunction "2_2") (pintype "passive"))
      (node (ref "R82") (pin "1") (pinfunction "1_1") (pintype "passive"))
      (node (ref "U5") (pin "2") (pinfunction "-IN_A_2") (pintype "input"))
    )
    (net (code "19") (name "Net-(U5--IN_B)") (class "Default")
      (node (ref "R19") (pin "2") (pinfunction "2_2") (pintype "passive"))
      (node (ref "R83") (pin "1") (pinfunction "1_1") (pintype "passive"))
      (node (ref "U5") (pin "6") (pinfunction "-IN_B_6") (pintype "input"))
    )
    (net (code "20") (name "Net-(U6-+IN_A)") (class "Default")
      (node (ref "R21") (pin "1") (pinfunction "1_1") (pintype "passive"))
      (node (ref "SENSORPANEL-0-16") (pin "4") (pinfunction "4_4") (pintype "passive"))
      (node (ref "U6") (pin "3") (pinfunction "+IN_A_3") (pintype "input"))
    )
    (net (code "21") (name "Net-(U6-+IN_B)") (class "Default")
      (node (ref "R22") (pin "1") (pinfunction "1_1") (pintype "passive"))
      (node (ref "SENSORPANEL-0-16") (pin "3") (pinfunction "3_3") (pintype "passive"))
      (node (ref "U6") (pin "5") (pinfunction "+IN_B_5") (pintype "input"))
    )
    (net (code "22") (name "Net-(U6--IN_A)") (class "Default")
      (node (ref "R20") (pin "2") (pinfunction "2_2") (pintype "passive"))
      (node (ref "R84") (pin "1") (pinfunction "1_1") (pintype "passive"))
      (node (ref "U6") (pin "2") (pinfunction "-IN_A_2") (pintype "input"))
    )
    (net (code "23") (name "Net-(U6--IN_B)") (class "Default")
      (node (ref "R23") (pin "2") (pinfunction "2_2") (pintype "passive"))
      (node (ref "R85") (pin "1") (pinfunction "1_1") (pintype "passive"))
      (node (ref "U6") (pin "6") (pinfunction "-IN_B_6") (pintype "input"))
    )
    (net (code "24") (name "Net-(U7-+IN_A)") (class "Default")
      (node (ref "R25") (pin "1") (pinfunction "1_1") (pintype "passive"))
      (node (ref "SENSORPANEL-0-16") (pin "6") (pinfunction "6_6") (pintype "passive"))
      (node (ref "U7") (pin "3") (pinfunction "+IN_A_3") (pintype "input"))
    )
    (net (code "25") (name "Net-(U7-+IN_B)") (class "Default")
      (node (ref "R26") (pin "1") (pinfunction "1_1") (pintype "passive"))
      (node (ref "SENSORPANEL-0-16") (pin "5") (pinfunction "5_5") (pintype "passive"))
      (node (ref "U7") (pin "5") (pinfunction "+IN_B_5") (pintype "input"))
    )
    (net (code "26") (name "Net-(U7--IN_A)") (class "Default")
      (node (ref "R24") (pin "1") (pinfunction "1_1") (pintype "passive"))
      (node (ref "R86") (pin "2") (pinfunction "2_2") (pintype "passive"))
      (node (ref "U7") (pin "2") (pinfunction "-IN_A_2") (pintype "input"))
    )
    (net (code "27") (name "Net-(U7--IN_B)") (class "Default")
      (node (ref "R27") (pin "2") (pinfunction "2_2") (pintype "passive"))
      (node (ref "R87") (pin "1") (pinfunction "1_1") (pintype "passive"))
      (node (ref "U7") (pin "6") (pinfunction "-IN_B_6") (pintype "input"))
    )
    (net (code "28") (name "Net-(U8-+IN_A)") (class "Default")
      (node (ref "R29") (pin "1") (pinfunction "1_1") (pintype "passive"))
      (node (ref "SENSORPANEL-0-16") (pin "8") (pinfunction "8_8") (pintype "passive"))
      (node (ref "U8") (pin "3") (pinfunction "+IN_A_3") (pintype "input"))
    )
    (net (code "29") (name "Net-(U8-+IN_B)") (class "Default")
      (node (ref "R30") (pin "1") (pinfunction "1_1") (pintype "passive"))
      (node (ref "SENSORPANEL-0-16") (pin "7") (pinfunction "7_7") (pintype "passive"))
      (node (ref "U8") (pin "5") (pinfunction "+IN_B_5") (pintype "input"))
    )
    (net (code "30") (name "Net-(U8--IN_A)") (class "Default")
      (node (ref "R28") (pin "2") (pinfunction "2_2") (pintype "passive"))
      (node (ref "R88") (pin "1") (pinfunction "1_1") (pintype "passive"))
      (node (ref "U8") (pin "2") (pinfunction "-IN_A_2") (pintype "input"))
    )
    (net (code "31") (name "Net-(U8--IN_B)") (class "Default")
      (node (ref "R31") (pin "2") (pinfunction "2_2") (pintype "passive"))
      (node (ref "R89") (pin "1") (pinfunction "1_1") (pintype "passive"))
      (node (ref "U8") (pin "6") (pinfunction "-IN_B_6") (pintype "input"))
    )
    (net (code "32") (name "Net-(U9-+IN_A)") (class "Default")
      (node (ref "R33") (pin "1") (pinfunction "1_1") (pintype "passive"))
      (node (ref "SENSORPANEL-0-16") (pin "10") (pinfunction "10_10") (pintype "passive"))
      (node (ref "U9") (pin "3") (pinfunction "+IN_A_3") (pintype "input"))
    )
    (net (code "33") (name "Net-(U9-+IN_B)") (class "Default")
      (node (ref "R34") (pin "1") (pinfunction "1_1") (pintype "passive"))
      (node (ref "SENSORPANEL-0-16") (pin "9") (pinfunction "9_9") (pintype "passive"))
      (node (ref "U9") (pin "5") (pinfunction "+IN_B_5") (pintype "input"))
    )
    (net (code "34") (name "Net-(U9--IN_A)") (class "Default")
      (node (ref "R32") (pin "1") (pinfunction "1_1") (pintype "passive"))
      (node (ref "R90") (pin "2") (pinfunction "2_2") (pintype "passive"))
      (node (ref "U9") (pin "2") (pinfunction "-IN_A_2") (pintype "input"))
    )
    (net (code "35") (name "Net-(U9--IN_B)") (class "Default")
      (node (ref "R35") (pin "2") (pinfunction "2_2") (pintype "passive"))
      (node (ref "R91") (pin "1") (pinfunction "1_1") (pintype "passive"))
      (node (ref "U9") (pin "6") (pinfunction "-IN_B_6") (pintype "input"))
    )
    (net (code "36") (name "Net-(U10-+IN_A)") (class "Default")
      (node (ref "R37") (pin "1") (pinfunction "1_1") (pintype "passive"))
      (node (ref "SENSORPANEL-0-16") (pin "12") (pinfunction "12_12") (pintype "passive"))
      (node (ref "U10") (pin "3") (pinfunction "+IN_A_3") (pintype "input"))
    )
    (net (code "37") (name "Net-(U10-+IN_B)") (class "Default")
      (node (ref "R38") (pin "1") (pinfunction "1_1") (pintype "passive"))
      (node (ref "SENSORPANEL-0-16") (pin "11") (pinfunction "11_11") (pintype "passive"))
      (node (ref "U10") (pin "5") (pinfunction "+IN_B_5") (pintype "input"))
    )
    (net (code "38") (name "Net-(U10--IN_A)") (class "Default")
      (node (ref "R36") (pin "1") (pinfunction "1_1") (pintype "passive"))
      (node (ref "R92") (pin "2") (pinfunction "2_2") (pintype "passive"))
      (node (ref "U10") (pin "2") (pinfunction "-IN_A_2") (pintype "input"))
    )
    (net (code "39") (name "Net-(U10--IN_B)") (class "Default")
      (node (ref "R39") (pin "2") (pinfunction "2_2") (pintype "passive"))
      (node (ref "R93") (pin "1") (pinfunction "1_1") (pintype "passive"))
      (node (ref "U10") (pin "6") (pinfunction "-IN_B_6") (pintype "input"))
    )
    (net (code "40") (name "Net-(U10-OUT_A)") (class "Default")
      (node (ref "R36") (pin "2") (pinfunction "2_2") (pintype "passive"))
      (node (ref "U10") (pin "1") (pinfunction "OUT_A_1") (pintype "output"))
      (node (ref "U14") (pin "12") (pinfunction "Y3_12") (pintype "bidirectional"))
    )
    (net (code "41") (name "Net-(U10-OUT_B)") (class "Default")
      (node (ref "R93") (pin "2") (pinfunction "2_2") (pintype "passive"))
      (node (ref "U10") (pin "7") (pinfunction "OUT_B_7") (pintype "output"))
      (node (ref "U14") (pin "15") (pinfunction "Y2_15") (pintype "bidirectional"))
    )
    (net (code "42") (name "Net-(U11-+IN_A)") (class "Default")
      (node (ref "R41") (pin "1") (pinfunction "1_1") (pintype "passive"))
      (node (ref "SENSORPANEL-0-16") (pin "14") (pinfunction "14_14") (pintype "passive"))
      (node (ref "U11") (pin "3") (pinfunction "+IN_A_3") (pintype "input"))
    )
    (net (code "43") (name "Net-(U11-+IN_B)") (class "Default")
      (node (ref "R42") (pin "1") (pinfunction "1_1") (pintype "passive"))
      (node (ref "SENSORPANEL-0-16") (pin "13") (pinfunction "13_13") (pintype "passive"))
      (node (ref "U11") (pin "5") (pinfunction "+IN_B_5") (pintype "input"))
    )
    (net (code "44") (name "Net-(U11--IN_A)") (class "Default")
      (node (ref "R40") (pin "2") (pinfunction "2_2") (pintype "passive"))
      (node (ref "R94") (pin "1") (pinfunction "1_1") (pintype "passive"))
      (node (ref "U11") (pin "2") (pinfunction "-IN_A_2") (pintype "input"))
    )
    (net (code "45") (name "Net-(U11--IN_B)") (class "Default")
      (node (ref "R43") (pin "2") (pinfunction "2_2") (pintype "passive"))
      (node (ref "R95") (pin "1") (pinfunction "1_1") (pintype "passive"))
      (node (ref "U11") (pin "6") (pinfunction "-IN_B_6") (pintype "input"))
    )
    (net (code "46") (name "Net-(U11-OUT_A)") (class "Default")
      (node (ref "R94") (pin "2") (pinfunction "2_2") (pintype "passive"))
      (node (ref "U11") (pin "1") (pinfunction "OUT_A_1") (pintype "output"))
      (node (ref "U14") (pin "5") (pinfunction "Y5_5") (pintype "bidirectional"))
    )
    (net (code "47") (name "Net-(U11-OUT_B)") (class "Default")
      (node (ref "R95") (pin "2") (pinfunction "2_2") (pintype "passive"))
      (node (ref "U11") (pin "7") (pinfunction "OUT_B_7") (pintype "output"))
      (node (ref "U14") (pin "1") (pinfunction "Y4_1") (pintype "bidirectional"))
    )
    (net (code "48") (name "Net-(U12-+IN_A)") (class "Default")
      (node (ref "R45") (pin "1") (pinfunction "1_1") (pintype "passive"))
      (node (ref "SENSORPANEL-0-16") (pin "16") (pinfunction "16_16") (pintype "passive"))
      (node (ref "U12") (pin "3") (pinfunction "+IN_A_3") (pintype "input"))
    )
    (net (code "49") (name "Net-(U12-+IN_B)") (class "Default")
      (node (ref "R46") (pin "1") (pinfunction "1_1") (pintype "passive"))
      (node (ref "SENSORPANEL-0-16") (pin "15") (pinfunction "15_15") (pintype "passive"))
      (node (ref "U12") (pin "5") (pinfunction "+IN_B_5") (pintype "input"))
    )
    (net (code "50") (name "Net-(U12--IN_A)") (class "Default")
      (node (ref "R44") (pin "2") (pinfunction "2_2") (pintype "passive"))
      (node (ref "R96") (pin "1") (pinfunction "1_1") (pintype "passive"))
      (node (ref "U12") (pin "2") (pinfunction "-IN_A_2") (pintype "input"))
    )
    (net (code "51") (name "Net-(U12--IN_B)") (class "Default")
      (node (ref "R47") (pin "2") (pinfunction "2_2") (pintype "passive"))
      (node (ref "R97") (pin "1") (pinfunction "1_1") (pintype "passive"))
      (node (ref "U12") (pin "6") (pinfunction "-IN_B_6") (pintype "input"))
    )
    (net (code "52") (name "Net-(U12-OUT_A)") (class "Default")
      (node (ref "R96") (pin "2") (pinfunction "2_2") (pintype "passive"))
      (node (ref "U12") (pin "1") (pinfunction "OUT_A_1") (pintype "output"))
      (node (ref "U14") (pin "4") (pinfunction "Y7_4") (pintype "bidirectional"))
    )
    (net (code "53") (name "Net-(U12-OUT_B)") (class "Default")
      (node (ref "R97") (pin "2") (pinfunction "2_2") (pintype "passive"))
      (node (ref "U12") (pin "7") (pinfunction "OUT_B_7") (pintype "output"))
      (node (ref "U14") (pin "2") (pinfunction "Y6_2") (pintype "bidirectional"))
    )
    (net (code "54") (name "Net-(U13-Y0)") (class "Default")
      (node (ref "R83") (pin "2") (pinfunction "2_2") (pintype "passive"))
      (node (ref "U13") (pin "13") (pinfunction "Y0_13") (pintype "bidirectional"))
      (node (ref "U5") (pin "7") (pinfunction "OUT_B_7") (pintype "output"))
    )
    (net (code "55") (name "Net-(U13-Y1)") (class "Default")
      (node (ref "R82") (pin "2") (pinfunction "2_2") (pintype "passive"))
      (node (ref "U13") (pin "14") (pinfunction "Y1_14") (pintype "bidirectional"))
      (node (ref "U5") (pin "1") (pinfunction "OUT_A_1") (pintype "output"))
    )
    (net (code "56") (name "Net-(U13-Y2)") (class "Default")
      (node (ref "R85") (pin "2") (pinfunction "2_2") (pintype "passive"))
      (node (ref "U13") (pin "15") (pinfunction "Y2_15") (pintype "bidirectional"))
      (node (ref "U6") (pin "7") (pinfunction "OUT_B_7") (pintype "output"))
    )
    (net (code "57") (name "Net-(U13-Y3)") (class "Default")
      (node (ref "R84") (pin "2") (pinfunction "2_2") (pintype "passive"))
      (node (ref "U13") (pin "12") (pinfunction "Y3_12") (pintype "bidirectional"))
      (node (ref "U6") (pin "1") (pinfunction "OUT_A_1") (pintype "output"))
    )
    (net (code "58") (name "Net-(U13-Y4)") (class "Default")
      (node (ref "R87") (pin "2") (pinfunction "2_2") (pintype "passive"))
      (node (ref "U13") (pin "1") (pinfunction "Y4_1") (pintype "bidirectional"))
      (node (ref "U7") (pin "7") (pinfunction "OUT_B_7") (pintype "output"))
    )
    (net (code "59") (name "Net-(U13-Y5)") (class "Default")
      (node (ref "R24") (pin "2") (pinfunction "2_2") (pintype "passive"))
      (node (ref "U13") (pin "5") (pinfunction "Y5_5") (pintype "bidirectional"))
      (node (ref "U7") (pin "1") (pinfunction "OUT_A_1") (pintype "output"))
    )
    (net (code "60") (name "Net-(U13-Y6)") (class "Default")
      (node (ref "R89") (pin "2") (pinfunction "2_2") (pintype "passive"))
      (node (ref "U13") (pin "2") (pinfunction "Y6_2") (pintype "bidirectional"))
      (node (ref "U8") (pin "7") (pinfunction "OUT_B_7") (pintype "output"))
    )
    (net (code "61") (name "Net-(U13-Y7)") (class "Default")
      (node (ref "R88") (pin "2") (pinfunction "2_2") (pintype "passive"))
      (node (ref "U13") (pin "4") (pinfunction "Y7_4") (pintype "bidirectional"))
      (node (ref "U8") (pin "1") (pinfunction "OUT_A_1") (pintype "output"))
    )
    (net (code "62") (name "Net-(U14-Y0)") (class "Default")
      (node (ref "R91") (pin "2") (pinfunction "2_2") (pintype "passive"))
      (node (ref "U14") (pin "13") (pinfunction "Y0_13") (pintype "bidirectional"))
      (node (ref "U9") (pin "7") (pinfunction "OUT_B_7") (pintype "output"))
    )
    (net (code "63") (name "Net-(U14-Y1)") (class "Default")
      (node (ref "R32") (pin "2") (pinfunction "2_2") (pintype "passive"))
      (node (ref "U14") (pin "14") (pinfunction "Y1_14") (pintype "bidirectional"))
      (node (ref "U9") (pin "1") (pinfunction "OUT_A_1") (pintype "output"))
    )
    (net (code "64") (name "Net-(U15-+IN_A)") (class "Default")
      (node (ref "R49") (pin "1") (pinfunction "1_1") (pintype "passive"))
      (node (ref "SENSORPANEL-16-31") (pin "2") (pinfunction "2_2") (pintype "passive"))
      (node (ref "U15") (pin "3") (pinfunction "+IN_A_3") (pintype "input"))
    )
    (net (code "65") (name "Net-(U15-+IN_B)") (class "Default")
      (node (ref "R50") (pin "1") (pinfunction "1_1") (pintype "passive"))
      (node (ref "SENSORPANEL-16-31") (pin "1") (pinfunction "1_1") (pintype "passive"))
      (node (ref "U15") (pin "5") (pinfunction "+IN_B_5") (pintype "input"))
    )
    (net (code "66") (name "Net-(U15--IN_A)") (class "Default")
      (node (ref "R2") (pin "1") (pinfunction "1_1") (pintype "passive"))
      (node (ref "R3") (pin "2") (pinfunction "2_2") (pintype "passive"))
      (node (ref "U15") (pin "2") (pinfunction "-IN_A_2") (pintype "input"))
    )
    (net (code "67") (name "Net-(U15--IN_B)") (class "Default")
      (node (ref "R4") (pin "2") (pinfunction "2_2") (pintype "passive"))
      (node (ref "R5") (pin "1") (pinfunction "1_1") (pintype "passive"))
      (node (ref "U15") (pin "6") (pinfunction "-IN_B_6") (pintype "input"))
    )
    (net (code "68") (name "Net-(U15-OUT_A)") (class "Default")
      (node (ref "R2") (pin "2") (pinfunction "2_2") (pintype "passive"))
      (node (ref "U15") (pin "1") (pinfunction "OUT_A_1") (pintype "output"))
      (node (ref "U23") (pin "14") (pinfunction "Y1_14") (pintype "bidirectional"))
    )
    (net (code "69") (name "Net-(U15-OUT_B)") (class "Default")
      (node (ref "R5") (pin "2") (pinfunction "2_2") (pintype "passive"))
      (node (ref "U15") (pin "7") (pinfunction "OUT_B_7") (pintype "output"))
      (node (ref "U23") (pin "13") (pinfunction "Y0_13") (pintype "bidirectional"))
    )
    (net (code "70") (name "Net-(U16-+IN_A)") (class "Default")
      (node (ref "R53") (pin "1") (pinfunction "1_1") (pintype "passive"))
      (node (ref "SENSORPANEL-16-31") (pin "4") (pinfunction "4_4") (pintype "passive"))
      (node (ref "U16") (pin "3") (pinfunction "+IN_A_3") (pintype "input"))
    )
    (net (code "71") (name "Net-(U16-+IN_B)") (class "Default")
      (node (ref "R54") (pin "1") (pinfunction "1_1") (pintype "passive"))
      (node (ref "SENSORPANEL-16-31") (pin "3") (pinfunction "3_3") (pintype "passive"))
      (node (ref "U16") (pin "5") (pinfunction "+IN_B_5") (pintype "input"))
    )
    (net (code "72") (name "Net-(U16--IN_A)") (class "Default")
      (node (ref "R6") (pin "2") (pinfunction "2_2") (pintype "passive"))
      (node (ref "R7") (pin "1") (pinfunction "1_1") (pintype "passive"))
      (node (ref "U16") (pin "2") (pinfunction "-IN_A_2") (pintype "input"))
    )
    (net (code "73") (name "Net-(U16--IN_B)") (class "Default")
      (node (ref "R8") (pin "2") (pinfunction "2_2") (pintype "passive"))
      (node (ref "R9") (pin "1") (pinfunction "1_1") (pintype "passive"))
      (node (ref "U16") (pin "6") (pinfunction "-IN_B_6") (pintype "input"))
    )
    (net (code "74") (name "Net-(U16-OUT_A)") (class "Default")
      (node (ref "R7") (pin "2") (pinfunction "2_2") (pintype "passive"))
      (node (ref "U16") (pin "1") (pinfunction "OUT_A_1") (pintype "output"))
      (node (ref "U23") (pin "12") (pinfunction "Y3_12") (pintype "bidirectional"))
    )
    (net (code "75") (name "Net-(U16-OUT_B)") (class "Default")
      (node (ref "R9") (pin "2") (pinfunction "2_2") (pintype "passive"))
      (node (ref "U16") (pin "7") (pinfunction "OUT_B_7") (pintype "output"))
      (node (ref "U23") (pin "15") (pinfunction "Y2_15") (pintype "bidirectional"))
    )
    (net (code "76") (name "Net-(U17-+IN_A)") (class "Default")
      (node (ref "R57") (pin "1") (pinfunction "1_1") (pintype "passive"))
      (node (ref "SENSORPANEL-16-31") (pin "6") (pinfunction "6_6") (pintype "passive"))
      (node (ref "U17") (pin "3") (pinfunction "+IN_A_3") (pintype "input"))
    )
    (net (code "77") (name "Net-(U17-+IN_B)") (class "Default")
      (node (ref "R58") (pin "1") (pinfunction "1_1") (pintype "passive"))
      (node (ref "SENSORPANEL-16-31") (pin "5") (pinfunction "5_5") (pintype "passive"))
      (node (ref "U17") (pin "5") (pinfunction "+IN_B_5") (pintype "input"))
    )
    (net (code "78") (name "Net-(U17--IN_A)") (class "Default")
      (node (ref "R10") (pin "1") (pinfunction "1_1") (pintype "passive"))
      (node (ref "R11") (pin "2") (pinfunction "2_2") (pintype "passive"))
      (node (ref "U17") (pin "2") (pinfunction "-IN_A_2") (pintype "input"))
    )
    (net (code "79") (name "Net-(U17--IN_B)") (class "Default")
      (node (ref "R12") (pin "2") (pinfunction "2_2") (pintype "passive"))
      (node (ref "R13") (pin "1") (pinfunction "1_1") (pintype "passive"))
      (node (ref "U17") (pin "6") (pinfunction "-IN_B_6") (pintype "input"))
    )
    (net (code "80") (name "Net-(U17-OUT_A)") (class "Default")
      (node (ref "R10") (pin "2") (pinfunction "2_2") (pintype "passive"))
      (node (ref "U17") (pin "1") (pinfunction "OUT_A_1") (pintype "output"))
      (node (ref "U23") (pin "5") (pinfunction "Y5_5") (pintype "bidirectional"))
    )
    (net (code "81") (name "Net-(U17-OUT_B)") (class "Default")
      (node (ref "R13") (pin "2") (pinfunction "2_2") (pintype "passive"))
      (node (ref "U17") (pin "7") (pinfunction "OUT_B_7") (pintype "output"))
      (node (ref "U23") (pin "1") (pinfunction "Y4_1") (pintype "bidirectional"))
    )
    (net (code "82") (name "Net-(U18-+IN_A)") (class "Default")
      (node (ref "R61") (pin "1") (pinfunction "1_1") (pintype "passive"))
      (node (ref "SENSORPANEL-16-31") (pin "8") (pinfunction "8_8") (pintype "passive"))
      (node (ref "U18") (pin "3") (pinfunction "+IN_A_3") (pintype "input"))
    )
    (net (code "83") (name "Net-(U18-+IN_B)") (class "Default")
      (node (ref "R62") (pin "1") (pinfunction "1_1") (pintype "passive"))
      (node (ref "SENSORPANEL-16-31") (pin "7") (pinfunction "7_7") (pintype "passive"))
      (node (ref "U18") (pin "5") (pinfunction "+IN_B_5") (pintype "input"))
    )
    (net (code "84") (name "Net-(U18--IN_A)") (class "Default")
      (node (ref "R14") (pin "2") (pinfunction "2_2") (pintype "passive"))
      (node (ref "R15") (pin "1") (pinfunction "1_1") (pintype "passive"))
      (node (ref "U18") (pin "2") (pinfunction "-IN_A_2") (pintype "input"))
    )
    (net (code "85") (name "Net-(U18--IN_B)") (class "Default")
      (node (ref "R48") (pin "2") (pinfunction "2_2") (pintype "passive"))
      (node (ref "R51") (pin "1") (pinfunction "1_1") (pintype "passive"))
      (node (ref "U18") (pin "6") (pinfunction "-IN_B_6") (pintype "input"))
    )
    (net (code "86") (name "Net-(U18-OUT_A)") (class "Default")
      (node (ref "R15") (pin "2") (pinfunction "2_2") (pintype "passive"))
      (node (ref "U18") (pin "1") (pinfunction "OUT_A_1") (pintype "output"))
      (node (ref "U23") (pin "4") (pinfunction "Y7_4") (pintype "bidirectional"))
    )
    (net (code "87") (name "Net-(U18-OUT_B)") (class "Default")
      (node (ref "R51") (pin "2") (pinfunction "2_2") (pintype "passive"))
      (node (ref "U18") (pin "7") (pinfunction "OUT_B_7") (pintype "output"))
      (node (ref "U23") (pin "2") (pinfunction "Y6_2") (pintype "bidirectional"))
    )
    (net (code "88") (name "Net-(U19-+IN_A)") (class "Default")
      (node (ref "R65") (pin "1") (pinfunction "1_1") (pintype "passive"))
      (node (ref "SENSORPANEL-16-31") (pin "10") (pinfunction "10_10") (pintype "passive"))
      (node (ref "U19") (pin "3") (pinfunction "+IN_A_3") (pintype "input"))
    )
    (net (code "89") (name "Net-(U19-+IN_B)") (class "Default")
      (node (ref "R66") (pin "1") (pinfunction "1_1") (pintype "passive"))
      (node (ref "SENSORPANEL-16-31") (pin "9") (pinfunction "9_9") (pintype "passive"))
      (node (ref "U19") (pin "5") (pinfunction "+IN_B_5") (pintype "input"))
    )
    (net (code "90") (name "Net-(U19--IN_A)") (class "Default")
      (node (ref "R52") (pin "2") (pinfunction "2_2") (pintype "passive"))
      (node (ref "R55") (pin "1") (pinfunction "1_1") (pintype "passive"))
      (node (ref "U19") (pin "2") (pinfunction "-IN_A_2") (pintype "input"))
    )
    (net (code "91") (name "Net-(U19--IN_B)") (class "Default")
      (node (ref "R56") (pin "2") (pinfunction "2_2") (pintype "passive"))
      (node (ref "R59") (pin "1") (pinfunction "1_1") (pintype "passive"))
      (node (ref "U19") (pin "6") (pinfunction "-IN_B_6") (pintype "input"))
    )
    (net (code "92") (name "Net-(U19-OUT_A)") (class "Default")
      (node (ref "R55") (pin "2") (pinfunction "2_2") (pintype "passive"))
      (node (ref "U19") (pin "1") (pinfunction "OUT_A_1") (pintype "output"))
      (node (ref "U24") (pin "14") (pinfunction "Y1_14") (pintype "bidirectional"))
    )
    (net (code "93") (name "Net-(U19-OUT_B)") (class "Default")
      (node (ref "R59") (pin "2") (pinfunction "2_2") (pintype "passive"))
      (node (ref "U19") (pin "7") (pinfunction "OUT_B_7") (pintype "output"))
      (node (ref "U24") (pin "13") (pinfunction "Y0_13") (pintype "bidirectional"))
    )
    (net (code "94") (name "Net-(U20-+IN_A)") (class "Default")
      (node (ref "R69") (pin "1") (pinfunction "1_1") (pintype "passive"))
      (node (ref "SENSORPANEL-16-31") (pin "12") (pinfunction "12_12") (pintype "passive"))
      (node (ref "U20") (pin "3") (pinfunction "+IN_A_3") (pintype "input"))
    )
    (net (code "95") (name "Net-(U20-+IN_B)") (class "Default")
      (node (ref "R70") (pin "1") (pinfunction "1_1") (pintype "passive"))
      (node (ref "SENSORPANEL-16-31") (pin "11") (pinfunction "11_11") (pintype "passive"))
      (node (ref "U20") (pin "5") (pinfunction "+IN_B_5") (pintype "input"))
    )
    (net (code "96") (name "Net-(U20--IN_A)") (class "Default")
      (node (ref "R60") (pin "2") (pinfunction "2_2") (pintype "passive"))
      (node (ref "R63") (pin "1") (pinfunction "1_1") (pintype "passive"))
      (node (ref "U20") (pin "2") (pinfunction "-IN_A_2") (pintype "input"))
    )
    (net (code "97") (name "Net-(U20--IN_B)") (class "Default")
      (node (ref "R64") (pin "2") (pinfunction "2_2") (pintype "passive"))
      (node (ref "R67") (pin "1") (pinfunction "1_1") (pintype "passive"))
      (node (ref "U20") (pin "6") (pinfunction "-IN_B_6") (pintype "input"))
    )
    (net (code "98") (name "Net-(U20-OUT_A)") (class "Default")
      (node (ref "R63") (pin "2") (pinfunction "2_2") (pintype "passive"))
      (node (ref "U20") (pin "1") (pinfunction "OUT_A_1") (pintype "output"))
      (node (ref "U24") (pin "12") (pinfunction "Y3_12") (pintype "bidirectional"))
    )
    (net (code "99") (name "Net-(U20-OUT_B)") (class "Default")
      (node (ref "R67") (pin "2") (pinfunction "2_2") (pintype "passive"))
      (node (ref "U20") (pin "7") (pinfunction "OUT_B_7") (pintype "output"))
      (node (ref "U24") (pin "15") (pinfunction "Y2_15") (pintype "bidirectional"))
    )
    (net (code "100") (name "Net-(U21-+IN_A)") (class "Default")
      (node (ref "R73") (pin "1") (pinfunction "1_1") (pintype "passive"))
      (node (ref "SENSORPANEL-16-31") (pin "14") (pinfunction "14_14") (pintype "passive"))
      (node (ref "U21") (pin "3") (pinfunction "+IN_A_3") (pintype "input"))
    )
    (net (code "101") (name "Net-(U21-+IN_B)") (class "Default")
      (node (ref "R74") (pin "1") (pinfunction "1_1") (pintype "passive"))
      (node (ref "SENSORPANEL-16-31") (pin "13") (pinfunction "13_13") (pintype "passive"))
      (node (ref "U21") (pin "5") (pinfunction "+IN_B_5") (pintype "input"))
    )
    (net (code "102") (name "Net-(U21--IN_A)") (class "Default")
      (node (ref "R68") (pin "2") (pinfunction "2_2") (pintype "passive"))
      (node (ref "R71") (pin "1") (pinfunction "1_1") (pintype "passive"))
      (node (ref "U21") (pin "2") (pinfunction "-IN_A_2") (pintype "input"))
    )
    (net (code "103") (name "Net-(U21--IN_B)") (class "Default")
      (node (ref "R72") (pin "2") (pinfunction "2_2") (pintype "passive"))
      (node (ref "R75") (pin "1") (pinfunction "1_1") (pintype "passive"))
      (node (ref "U21") (pin "6") (pinfunction "-IN_B_6") (pintype "input"))
    )
    (net (code "104") (name "Net-(U21-OUT_A)") (class "Default")
      (node (ref "R71") (pin "2") (pinfunction "2_2") (pintype "passive"))
      (node (ref "U21") (pin "1") (pinfunction "OUT_A_1") (pintype "output"))
      (node (ref "U24") (pin "5") (pinfunction "Y5_5") (pintype "bidirectional"))
    )
    (net (code "105") (name "Net-(U21-OUT_B)") (class "Default")
      (node (ref "R75") (pin "2") (pinfunction "2_2") (pintype "passive"))
      (node (ref "U21") (pin "7") (pinfunction "OUT_B_7") (pintype "output"))
      (node (ref "U24") (pin "1") (pinfunction "Y4_1") (pintype "bidirectional"))
    )
    (net (code "106") (name "Net-(U22-+IN_A)") (class "Default")
      (node (ref "R77") (pin "1") (pinfunction "1_1") (pintype "passive"))
      (node (ref "SENSORPANEL-16-31") (pin "16") (pinfunction "16_16") (pintype "passive"))
      (node (ref "U22") (pin "3") (pinfunction "+IN_A_3") (pintype "input"))
    )
    (net (code "107") (name "Net-(U22-+IN_B)") (class "Default")
      (node (ref "R78") (pin "1") (pinfunction "1_1") (pintype "passive"))
      (node (ref "SENSORPANEL-16-31") (pin "15") (pinfunction "15_15") (pintype "passive"))
      (node (ref "U22") (pin "5") (pinfunction "+IN_B_5") (pintype "input"))
    )
    (net (code "108") (name "Net-(U22--IN_A)") (class "Default")
      (node (ref "R76") (pin "2") (pinfunction "2_2") (pintype "passive"))
      (node (ref "R80") (pin "1") (pinfunction "1_1") (pintype "passive"))
      (node (ref "U22") (pin "2") (pinfunction "-IN_A_2") (pintype "input"))
    )
    (net (code "109") (name "Net-(U22--IN_B)") (class "Default")
      (node (ref "R79") (pin "2") (pinfunction "2_2") (pintype "passive"))
      (node (ref "R81") (pin "1") (pinfunction "1_1") (pintype "passive"))
      (node (ref "U22") (pin "6") (pinfunction "-IN_B_6") (pintype "input"))
    )
    (net (code "110") (name "Net-(U22-OUT_A)") (class "Default")
      (node (ref "R80") (pin "2") (pinfunction "2_2") (pintype "passive"))
      (node (ref "U22") (pin "1") (pinfunction "OUT_A_1") (pintype "output"))
      (node (ref "U24") (pin "4") (pinfunction "Y7_4") (pintype "bidirectional"))
    )
    (net (code "111") (name "Net-(U22-OUT_B)") (class "Default")
      (node (ref "R81") (pin "2") (pinfunction "2_2") (pintype "passive"))
      (node (ref "U22") (pin "7") (pinfunction "OUT_B_7") (pintype "output"))
      (node (ref "U24") (pin "2") (pinfunction "Y6_2") (pintype "bidirectional"))
    )
    (net (code "112") (name "unconnected-(IC2-QH*-Pad9)") (class "Default")
      (node (ref "IC2") (pin "9") (pinfunction "QH*_9") (pintype "tri_state"))
    )
    (net (code "113") (name "unconnected-(IC2-QH-Pad7)") (class "Default")
      (node (ref "IC2") (pin "7") (pinfunction "QH_7") (pintype "tri_state"))
    )
    (net (code "114") (name "unconnected-(MAINBOARD-Pad7)") (class "Default")
      (node (ref "MAINBOARD") (pin "7") (pinfunction "7_7") (pintype "passive"))
    )
  )
)
